# TF-USB.net
KiCad netlist of a schematic drawn in Altium Designer
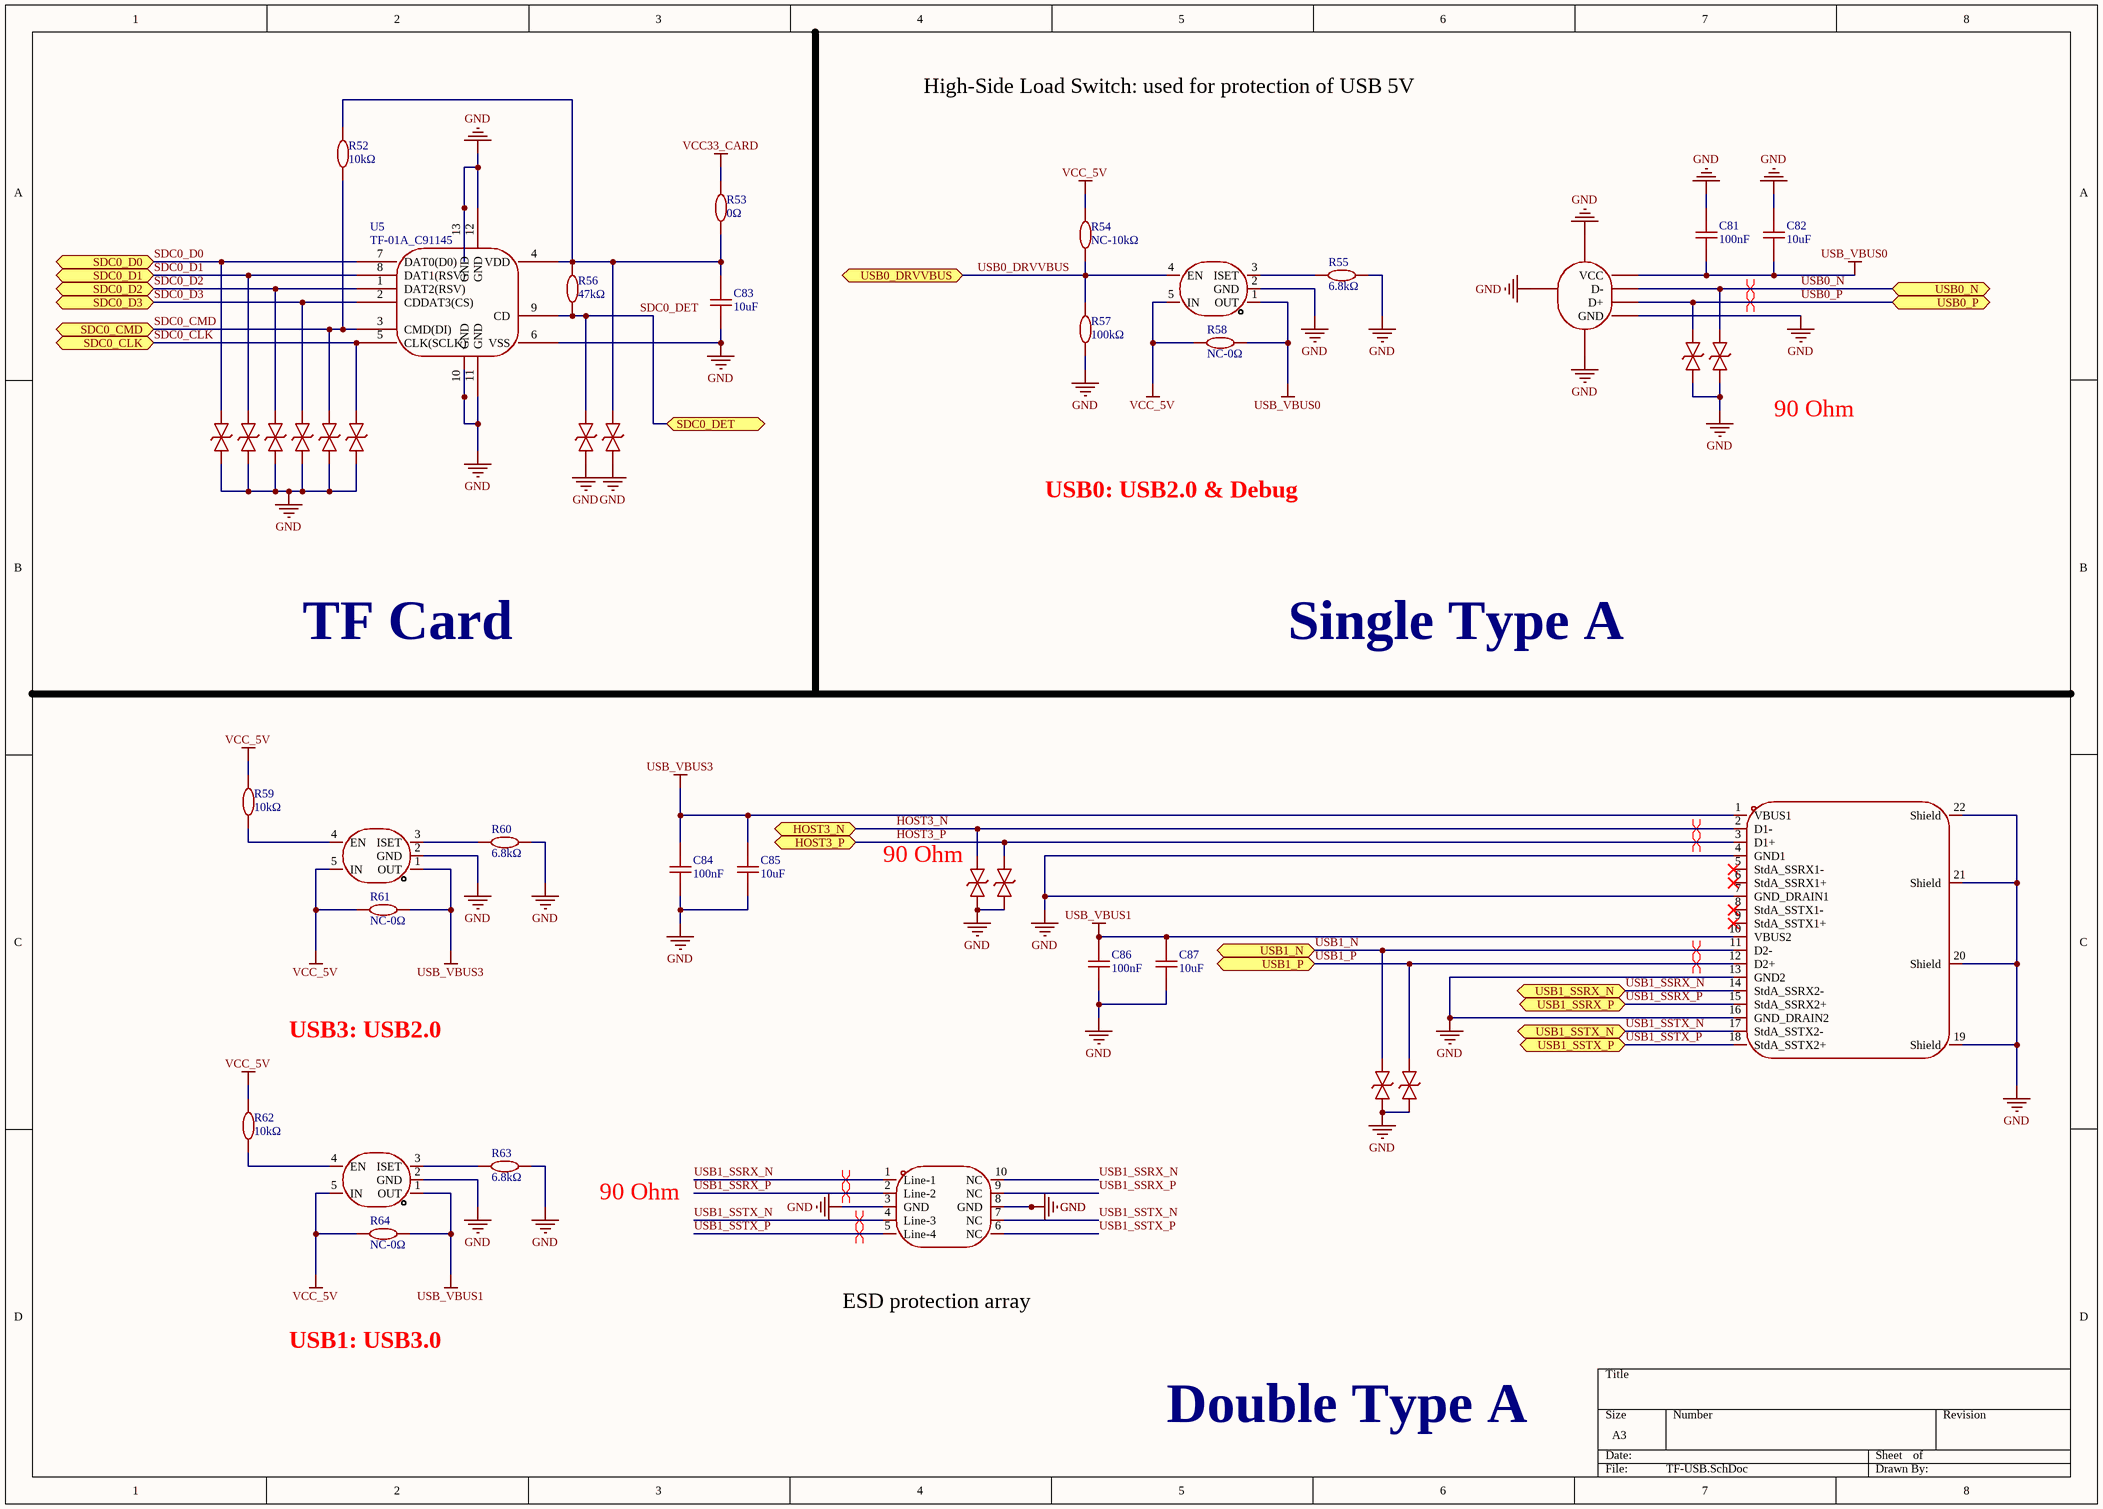
[diagram p0: TF-USB.SchDoc]

(export (version "E")
  (design (tool "Eeschema 10.0.6"))
  (components
    (comp (ref "C81")
      (value "100nF")
      (footprint "C0402")
      (description "50V 100nF X7R ±10% 0402 Ceramic Capacitors ROHS")
      (libsource (lib "RLC") (part "100nF"))
    )
    (comp (ref "C82")
      (value "10uF")
      (footprint "C0603")
      (description "10V 10uF X5R ±10% 0603 Ceramic Capacitors ROHS")
      (libsource (lib "RLC") (part "10uF"))
    )
    (comp (ref "C83")
      (value "10uF")
      (footprint "C0603")
      (description "10V 10uF X5R ±10% 0603 Ceramic Capacitors ROHS")
      (libsource (lib "RLC") (part "10uF"))
    )
    (comp (ref "C84")
      (value "100nF")
      (footprint "C0402")
      (description "50V 100nF X7R ±10% 0402 Ceramic Capacitors ROHS")
      (libsource (lib "RLC") (part "100nF"))
    )
    (comp (ref "C85")
      (value "10uF")
      (footprint "C0603")
      (description "10V 10uF X5R ±10% 0603 Ceramic Capacitors ROHS")
      (libsource (lib "RLC") (part "10uF"))
    )
    (comp (ref "C86")
      (value "100nF")
      (footprint "C0402")
      (description "50V 100nF X7R ±10% 0402 Ceramic Capacitors ROHS")
      (libsource (lib "RLC") (part "100nF"))
    )
    (comp (ref "C87")
      (value "10uF")
      (footprint "C0603")
      (description "10V 10uF X5R ±10% 0603 Ceramic Capacitors ROHS")
      (libsource (lib "RLC") (part "10uF"))
    )
    (comp (ref "D6")
      (value "AZ1045-04F.R7G")
      (footprint "DFN2510-10_L2.5-W1.0-P0.50-BL")
      (description "3.5A@8/20us 30W@8/20us 12V 6V 5V DFN2510-10 TVS Diodes ROHS")
      (fields (field (name "MANUFACTURER") "AMAZING(晶焱)"))
      (libsource (lib "IC") (part "AZ1045-04F.R7G"))
    )
    (comp (ref "R52")
      (value "10kΩ")
      (footprint "R0402")
      (description "62.5mW 10kΩ 50V ±100ppm/℃ Thick Film Resistor ±1% 0402 Chip Resistor - Surface Mount ROHS")
      (libsource (lib "RLC") (part "10kΩ"))
    )
    (comp (ref "R53")
      (value "0Ω")
      (footprint "R0402")
      (description "0Ω 62.5mW 50V Thick Film Resistor ±1% 0402 Chip Resistor - Surface Mount ROHS")
      (libsource (lib "RLC") (part "0Ω"))
    )
    (comp (ref "R54")
      (value "NC-10kΩ")
      (footprint "R0402")
      (description "62.5mW 10kΩ 50V ±100ppm/℃ Thick Film Resistor ±1% 0402 Chip Resistor - Surface Mount ROHS")
      (libsource (lib "RLC") (part "10kΩ"))
    )
    (comp (ref "R55")
      (value "6.8kΩ")
      (footprint "R0402")
      (description "62.5mW 6.8kΩ 50V ±100ppm/℃ Thick Film Resistor ±1% 0402 Chip Resistor - Surface Mount ROHS")
      (libsource (lib "RLC") (part "6.8kΩ"))
    )
    (comp (ref "R56")
      (value "47kΩ")
      (footprint "R0402")
      (description "62.5mW 47kΩ 50V ±100ppm/℃ Thick Film Resistor ±1% 0402 Chip Resistor - Surface Mount ROHS")
      (libsource (lib "RLC") (part "47kΩ"))
    )
    (comp (ref "R57")
      (value "100kΩ")
      (footprint "R0402")
      (description "100kΩ 62.5mW 50V ±100ppm/℃ Thick Film Resistor ±1% 0402 Chip Resistor - Surface Mount ROHS")
      (libsource (lib "RLC") (part "100kΩ"))
    )
    (comp (ref "R58")
      (value "NC-0Ω")
      (footprint "R0402")
      (description "0Ω 62.5mW 50V Thick Film Resistor ±1% 0402 Chip Resistor - Surface Mount ROHS")
      (libsource (lib "RLC") (part "0Ω"))
    )
    (comp (ref "R59")
      (value "10kΩ")
      (footprint "R0402")
      (description "62.5mW 10kΩ 50V ±100ppm/℃ Thick Film Resistor ±1% 0402 Chip Resistor - Surface Mount ROHS")
      (libsource (lib "RLC") (part "10kΩ"))
    )
    (comp (ref "R60")
      (value "6.8kΩ")
      (footprint "R0402")
      (description "62.5mW 6.8kΩ 50V ±100ppm/℃ Thick Film Resistor ±1% 0402 Chip Resistor - Surface Mount ROHS")
      (libsource (lib "RLC") (part "6.8kΩ"))
    )
    (comp (ref "R61")
      (value "NC-0Ω")
      (footprint "R0402")
      (description "0Ω 62.5mW 50V Thick Film Resistor ±1% 0402 Chip Resistor - Surface Mount ROHS")
      (libsource (lib "RLC") (part "0Ω"))
    )
    (comp (ref "R62")
      (value "10kΩ")
      (footprint "R0402")
      (description "62.5mW 10kΩ 50V ±100ppm/℃ Thick Film Resistor ±1% 0402 Chip Resistor - Surface Mount ROHS")
      (libsource (lib "RLC") (part "10kΩ"))
    )
    (comp (ref "R63")
      (value "6.8kΩ")
      (footprint "R0402")
      (description "62.5mW 6.8kΩ 50V ±100ppm/℃ Thick Film Resistor ±1% 0402 Chip Resistor - Surface Mount ROHS")
      (libsource (lib "RLC") (part "6.8kΩ"))
    )
    (comp (ref "R64")
      (value "NC-0Ω")
      (footprint "R0402")
      (description "0Ω 62.5mW 50V Thick Film Resistor ±1% 0402 Chip Resistor - Surface Mount ROHS")
      (libsource (lib "RLC") (part "0Ω"))
    )
    (comp (ref "U5")
      (value "TF-01A_C91145")
      (footprint "TF-SMD_TF-01A")
      (description "Push-Push 1.85mm Connector and Ejector MicroSD Card (TF Card) SMD PC Card Sockets ROHS")
      (libsource (lib "IC") (part "TF-01A_C91145"))
    )
    (comp (ref "U13")
      (value "SY6280AAC")
      (footprint "SOT-23-5_L3.0-W1.7-P0.95-LS2.8-BL")
      (description "1 Active High High Side Switch SOT-23-5 Power Distribution Switches, Load Drivers ROHS")
      (fields (field (name "MANUFACTURER") "Silergy(矽力杰)"))
      (libsource (lib "Switch") (part "SY6280AAC_C55136"))
    )
    (comp (ref "U14")
      (value "ESD5451N")
      (footprint "DFN1006-2L-BI")
      (description "9A 9.8V 8V Bidirectional 5V DFN1006-2L TVS Diodes ROHS")
      (fields (field (name "MANUFACTURER") "HXY MOSFET(华轩阳电子)"))
      (libsource (lib "LED") (part "ESD5451N_C5261080"))
    )
    (comp (ref "U15")
      (value "ESD5451N")
      (footprint "DFN1006-2L-BI")
      (description "9A 9.8V 8V Bidirectional 5V DFN1006-2L TVS Diodes ROHS")
      (fields (field (name "MANUFACTURER") "HXY MOSFET(华轩阳电子)"))
      (libsource (lib "LED") (part "ESD5451N_C5261080"))
    )
    (comp (ref "U16")
      (value "ESD5451N")
      (footprint "DFN1006-2L-BI")
      (description "9A 9.8V 8V Bidirectional 5V DFN1006-2L TVS Diodes ROHS")
      (fields (field (name "MANUFACTURER") "HXY MOSFET(华轩阳电子)"))
      (libsource (lib "LED") (part "ESD5451N_C5261080"))
    )
    (comp (ref "U17")
      (value "ESD5451N")
      (footprint "DFN1006-2L-BI")
      (description "9A 9.8V 8V Bidirectional 5V DFN1006-2L TVS Diodes ROHS")
      (fields (field (name "MANUFACTURER") "HXY MOSFET(华轩阳电子)"))
      (libsource (lib "LED") (part "ESD5451N_C5261080"))
    )
    (comp (ref "U18")
      (value "ESD5451N")
      (footprint "DFN1006-2L-BI")
      (description "9A 9.8V 8V Bidirectional 5V DFN1006-2L TVS Diodes ROHS")
      (fields (field (name "MANUFACTURER") "HXY MOSFET(华轩阳电子)"))
      (libsource (lib "LED") (part "ESD5451N_C5261080"))
    )
    (comp (ref "U19")
      (value "ESD5451N")
      (footprint "DFN1006-2L-BI")
      (description "9A 9.8V 8V Bidirectional 5V DFN1006-2L TVS Diodes ROHS")
      (fields (field (name "MANUFACTURER") "HXY MOSFET(华轩阳电子)"))
      (libsource (lib "LED") (part "ESD5451N_C5261080"))
    )
    (comp (ref "U20")
      (value "ESD5451N")
      (footprint "DFN1006-2L-BI")
      (description "9A 9.8V 8V Bidirectional 5V DFN1006-2L TVS Diodes ROHS")
      (fields (field (name "MANUFACTURER") "HXY MOSFET(华轩阳电子)"))
      (libsource (lib "LED") (part "ESD5451N_C5261080"))
    )
    (comp (ref "U21")
      (value "ESD5451N")
      (footprint "DFN1006-2L-BI")
      (description "9A 9.8V 8V Bidirectional 5V DFN1006-2L TVS Diodes ROHS")
      (fields (field (name "MANUFACTURER") "HXY MOSFET(华轩阳电子)"))
      (libsource (lib "LED") (part "ESD5451N_C5261080"))
    )
    (comp (ref "U22")
      (value "ESD5451N")
      (footprint "DFN1006-2L-BI")
      (description "9A 9.8V 8V Bidirectional 5V DFN1006-2L TVS Diodes ROHS")
      (fields (field (name "MANUFACTURER") "HXY MOSFET(华轩阳电子)"))
      (libsource (lib "LED") (part "ESD5451N_C5261080"))
    )
    (comp (ref "U23")
      (value "ESD5451N")
      (footprint "DFN1006-2L-BI")
      (description "9A 9.8V 8V Bidirectional 5V DFN1006-2L TVS Diodes ROHS")
      (fields (field (name "MANUFACTURER") "HXY MOSFET(华轩阳电子)"))
      (libsource (lib "LED") (part "ESD5451N_C5261080"))
    )
    (comp (ref "U24")
      (value "ESD5451N")
      (footprint "DFN1006-2L-BI")
      (description "9A 9.8V 8V Bidirectional 5V DFN1006-2L TVS Diodes ROHS")
      (fields (field (name "MANUFACTURER") "HXY MOSFET(华轩阳电子)"))
      (libsource (lib "LED") (part "ESD5451N_C5261080"))
    )
    (comp (ref "U25")
      (value "ESD5451N")
      (footprint "DFN1006-2L-BI")
      (description "9A 9.8V 8V Bidirectional 5V DFN1006-2L TVS Diodes ROHS")
      (fields (field (name "MANUFACTURER") "HXY MOSFET(华轩阳电子)"))
      (libsource (lib "LED") (part "ESD5451N_C5261080"))
    )
    (comp (ref "U26")
      (value "SY6280AAC")
      (footprint "SOT-23-5_L3.0-W1.7-P0.95-LS2.8-BL")
      (description "1 Active High High Side Switch SOT-23-5 Power Distribution Switches, Load Drivers ROHS")
      (fields (field (name "MANUFACTURER") "Silergy(矽力杰)"))
      (libsource (lib "Switch") (part "SY6280AAC_C55136"))
    )
    (comp (ref "U27")
      (value "ESD5451N")
      (footprint "DFN1006-2L-BI")
      (description "9A 9.8V 8V Bidirectional 5V DFN1006-2L TVS Diodes ROHS")
      (fields (field (name "MANUFACTURER") "HXY MOSFET(华轩阳电子)"))
      (libsource (lib "LED") (part "ESD5451N_C5261080"))
    )
    (comp (ref "U28")
      (value "ESD5451N")
      (footprint "DFN1006-2L-BI")
      (description "9A 9.8V 8V Bidirectional 5V DFN1006-2L TVS Diodes ROHS")
      (fields (field (name "MANUFACTURER") "HXY MOSFET(华轩阳电子)"))
      (libsource (lib "LED") (part "ESD5451N_C5261080"))
    )
    (comp (ref "U29")
      (value "SY6280AAC")
      (footprint "SOT-23-5_L3.0-W1.7-P0.95-LS2.8-BL")
      (description "1 Active High High Side Switch SOT-23-5 Power Distribution Switches, Load Drivers ROHS")
      (fields (field (name "MANUFACTURER") "Silergy(矽力杰)"))
      (libsource (lib "Switch") (part "SY6280AAC_C55136"))
    )
    (comp (ref "USB1")
      (value "USB-303WSD-BRY")
      (footprint "USB-A-TH_XUNPU_USB-303WSD-BRY")
      (description "USB 3.0 2 9Px2 -30℃~+85℃ Type-A Through Hole,Right Angle USB, DVI, HDMI Connector Assemblies ROHS")
      (fields (field (name "MANUFACTURER") "XUNPU(讯普)"))
      (libsource (lib "Connector") (part "USB-303WSD-BRY"))
    )
    (comp (ref "USB2")
      (value "906-162A1011D10200")
      (footprint "USB-A-TH_4P-P1.40-V-F-C39416")
      (description "USB 2.0 1 4P Type-A Through Hole USB, DVI, HDMI Connector Assemblies ROHS")
      (fields (field (name "MANUFACTURER") "精拓金"))
      (libsource (lib "Connector") (part "906-162A1011D10200"))
    )
  )
  (nets
    (net (code "1") (name "/HOST3_N") (class "Default")
      (node (ref "U24") (pin "2") (pinfunction "2_2") (pintype "passive"))
      (node (ref "USB1") (pin "2") (pinfunction "D1-_2") (pintype "passive"))
    )
    (net (code "2") (name "/HOST3_P") (class "Default")
      (node (ref "U25") (pin "2") (pinfunction "2_2") (pintype "passive"))
      (node (ref "USB1") (pin "3") (pinfunction "D1+_3") (pintype "passive"))
    )
    (net (code "3") (name "/SDC0_CLK") (class "Default")
      (node (ref "U21") (pin "2") (pinfunction "2_2") (pintype "passive"))
      (node (ref "U5") (pin "5") (pinfunction "CLK(SCLK)_5") (pintype "passive"))
    )
    (net (code "4") (name "/SDC0_CMD") (class "Default")
      (node (ref "R52") (pin "1") (pinfunction "1_1") (pintype "passive"))
      (node (ref "U20") (pin "2") (pinfunction "2_2") (pintype "passive"))
      (node (ref "U5") (pin "3") (pinfunction "CMD(DI)_3") (pintype "passive"))
    )
    (net (code "5") (name "/SDC0_D0") (class "Default")
      (node (ref "U16") (pin "2") (pinfunction "2_2") (pintype "passive"))
      (node (ref "U5") (pin "7") (pinfunction "DAT0(D0)_7") (pintype "passive"))
    )
    (net (code "6") (name "/SDC0_D1") (class "Default")
      (node (ref "U17") (pin "2") (pinfunction "2_2") (pintype "passive"))
      (node (ref "U5") (pin "8") (pinfunction "DAT1(RSV)_8") (pintype "passive"))
    )
    (net (code "7") (name "/SDC0_D2") (class "Default")
      (node (ref "U18") (pin "2") (pinfunction "2_2") (pintype "passive"))
      (node (ref "U5") (pin "1") (pinfunction "DAT2(RSV)_1") (pintype "passive"))
    )
    (net (code "8") (name "/SDC0_D3") (class "Default")
      (node (ref "U19") (pin "2") (pinfunction "2_2") (pintype "passive"))
      (node (ref "U5") (pin "2") (pinfunction "CDDAT3(CS)_2") (pintype "passive"))
    )
    (net (code "9") (name "/SDC0_DET") (class "Default")
      (node (ref "R56") (pin "1") (pinfunction "1_1") (pintype "passive"))
      (node (ref "U22") (pin "2") (pinfunction "2_2") (pintype "passive"))
      (node (ref "U5") (pin "9") (pinfunction "CD_9") (pintype "passive"))
    )
    (net (code "10") (name "/USB0_DRVVBUS") (class "Default")
      (node (ref "R54") (pin "1") (pinfunction "1_1") (pintype "passive"))
      (node (ref "R57") (pin "2") (pinfunction "2_2") (pintype "passive"))
      (node (ref "U13") (pin "4") (pinfunction "EN_4") (pintype "passive"))
    )
    (net (code "11") (name "/USB0_N") (class "Default")
      (node (ref "U15") (pin "2") (pinfunction "2_2") (pintype "passive"))
      (node (ref "USB2") (pin "2") (pinfunction "D-_2") (pintype "passive"))
    )
    (net (code "12") (name "/USB0_P") (class "Default")
      (node (ref "U14") (pin "2") (pinfunction "2_2") (pintype "passive"))
      (node (ref "USB2") (pin "3") (pinfunction "D+_3") (pintype "passive"))
    )
    (net (code "13") (name "/USB1_N") (class "Default")
      (node (ref "U27") (pin "2") (pinfunction "2_2") (pintype "passive"))
      (node (ref "USB1") (pin "11") (pinfunction "D2-_11") (pintype "passive"))
    )
    (net (code "14") (name "/USB1_P") (class "Default")
      (node (ref "U28") (pin "2") (pinfunction "2_2") (pintype "passive"))
      (node (ref "USB1") (pin "12") (pinfunction "D2+_12") (pintype "passive"))
    )
    (net (code "15") (name "/USB1_SSRX_N") (class "Default")
      (node (ref "D6") (pin "1") (pinfunction "Line-1_1") (pintype "passive"))
      (node (ref "D6") (pin "10") (pinfunction "NC_10") (pintype "passive"))
      (node (ref "USB1") (pin "14") (pinfunction "StdA_SSRX2-_14") (pintype "passive"))
    )
    (net (code "16") (name "/USB1_SSRX_P") (class "Default")
      (node (ref "D6") (pin "2") (pinfunction "Line-2_2") (pintype "passive"))
      (node (ref "D6") (pin "9") (pinfunction "NC_9") (pintype "passive"))
      (node (ref "USB1") (pin "15") (pinfunction "StdA_SSRX2+_15") (pintype "passive"))
    )
    (net (code "17") (name "/USB1_SSTX_N") (class "Default")
      (node (ref "D6") (pin "4") (pinfunction "Line-3_4") (pintype "passive"))
      (node (ref "D6") (pin "7") (pinfunction "NC_7") (pintype "passive"))
      (node (ref "USB1") (pin "17") (pinfunction "StdA_SSTX2-_17") (pintype "passive"))
    )
    (net (code "18") (name "/USB1_SSTX_P") (class "Default")
      (node (ref "D6") (pin "5") (pinfunction "Line-4_5") (pintype "passive"))
      (node (ref "D6") (pin "6") (pinfunction "NC_6") (pintype "passive"))
      (node (ref "USB1") (pin "18") (pinfunction "StdA_SSTX2+_18") (pintype "passive"))
    )
    (net (code "19") (name "GND") (class "Default")
      (node (ref "C81") (pin "2") (pinfunction "2_2") (pintype "passive"))
      (node (ref "C82") (pin "2") (pinfunction "2_2") (pintype "passive"))
      (node (ref "C83") (pin "1") (pinfunction "1_1") (pintype "passive"))
      (node (ref "C84") (pin "1") (pinfunction "1_1") (pintype "passive"))
      (node (ref "C85") (pin "1") (pinfunction "1_1") (pintype "passive"))
      (node (ref "C86") (pin "1") (pinfunction "1_1") (pintype "passive"))
      (node (ref "C87") (pin "1") (pinfunction "1_1") (pintype "passive"))
      (node (ref "D6") (pin "3") (pinfunction "GND_3") (pintype "passive"))
      (node (ref "D6") (pin "8") (pinfunction "GND_8") (pintype "passive"))
      (node (ref "R55") (pin "2") (pinfunction "2_2") (pintype "passive"))
      (node (ref "R57") (pin "1") (pinfunction "1_1") (pintype "passive"))
      (node (ref "R60") (pin "2") (pinfunction "2_2") (pintype "passive"))
      (node (ref "R63") (pin "2") (pinfunction "2_2") (pintype "passive"))
      (node (ref "U13") (pin "2") (pinfunction "GND_2") (pintype "passive"))
      (node (ref "U14") (pin "1") (pinfunction "1_1") (pintype "passive"))
      (node (ref "U15") (pin "1") (pinfunction "1_1") (pintype "passive"))
      (node (ref "U16") (pin "1") (pinfunction "1_1") (pintype "passive"))
      (node (ref "U17") (pin "1") (pinfunction "1_1") (pintype "passive"))
      (node (ref "U18") (pin "1") (pinfunction "1_1") (pintype "passive"))
      (node (ref "U19") (pin "1") (pinfunction "1_1") (pintype "passive"))
      (node (ref "U20") (pin "1") (pinfunction "1_1") (pintype "passive"))
      (node (ref "U21") (pin "1") (pinfunction "1_1") (pintype "passive"))
      (node (ref "U22") (pin "1") (pinfunction "1_1") (pintype "passive"))
      (node (ref "U23") (pin "1") (pinfunction "1_1") (pintype "passive"))
      (node (ref "U24") (pin "1") (pinfunction "1_1") (pintype "passive"))
      (node (ref "U25") (pin "1") (pinfunction "1_1") (pintype "passive"))
      (node (ref "U26") (pin "2") (pinfunction "GND_2") (pintype "passive"))
      (node (ref "U27") (pin "1") (pinfunction "1_1") (pintype "passive"))
      (node (ref "U28") (pin "1") (pinfunction "1_1") (pintype "passive"))
      (node (ref "U29") (pin "2") (pinfunction "GND_2") (pintype "passive"))
      (node (ref "U5") (pin "10") (pinfunction "GND_10") (pintype "passive"))
      (node (ref "U5") (pin "11") (pinfunction "GND_11") (pintype "passive"))
      (node (ref "U5") (pin "12") (pinfunction "GND_12") (pintype "passive"))
      (node (ref "U5") (pin "13") (pinfunction "GND_13") (pintype "passive"))
      (node (ref "U5") (pin "6") (pinfunction "VSS_6") (pintype "passive"))
      (node (ref "USB1") (pin "13") (pinfunction "GND2_13") (pintype "passive"))
      (node (ref "USB1") (pin "16") (pinfunction "GND_DRAIN2_16") (pintype "passive"))
      (node (ref "USB1") (pin "19") (pinfunction "Shield_19") (pintype "passive"))
      (node (ref "USB1") (pin "20") (pinfunction "Shield_20") (pintype "passive"))
      (node (ref "USB1") (pin "21") (pinfunction "Shield_21") (pintype "passive"))
      (node (ref "USB1") (pin "22") (pinfunction "Shield_22") (pintype "passive"))
      (node (ref "USB1") (pin "4") (pinfunction "GND1_4") (pintype "passive"))
      (node (ref "USB1") (pin "7") (pinfunction "GND_DRAIN1_7") (pintype "passive"))
      (node (ref "USB2") (pin "4") (pinfunction "GND_4") (pintype "passive"))
      (node (ref "USB2") (pin "5") (pinfunction "5_5") (pintype "passive"))
      (node (ref "USB2") (pin "6") (pinfunction "6_6") (pintype "passive"))
      (node (ref "USB2") (pin "7") (pinfunction "7_7") (pintype "passive"))
    )
    (net (code "20") (name "Net-(U5-VDD)") (class "Default")
      (node (ref "C83") (pin "2") (pinfunction "2_2") (pintype "passive"))
      (node (ref "R52") (pin "2") (pinfunction "2_2") (pintype "passive"))
      (node (ref "R53") (pin "1") (pinfunction "1_1") (pintype "passive"))
      (node (ref "R56") (pin "2") (pinfunction "2_2") (pintype "passive"))
      (node (ref "U23") (pin "2") (pinfunction "2_2") (pintype "passive"))
      (node (ref "U5") (pin "4") (pinfunction "VDD_4") (pintype "passive"))
    )
    (net (code "21") (name "Net-(U13-ISET)") (class "Default")
      (node (ref "R55") (pin "1") (pinfunction "1_1") (pintype "passive"))
      (node (ref "U13") (pin "3") (pinfunction "ISET_3") (pintype "passive"))
    )
    (net (code "22") (name "Net-(U26-EN)") (class "Default")
      (node (ref "R59") (pin "1") (pinfunction "1_1") (pintype "passive"))
      (node (ref "U26") (pin "4") (pinfunction "EN_4") (pintype "passive"))
    )
    (net (code "23") (name "Net-(U26-ISET)") (class "Default")
      (node (ref "R60") (pin "1") (pinfunction "1_1") (pintype "passive"))
      (node (ref "U26") (pin "3") (pinfunction "ISET_3") (pintype "passive"))
    )
    (net (code "24") (name "Net-(U29-EN)") (class "Default")
      (node (ref "R62") (pin "1") (pinfunction "1_1") (pintype "passive"))
      (node (ref "U29") (pin "4") (pinfunction "EN_4") (pintype "passive"))
    )
    (net (code "25") (name "Net-(U29-ISET)") (class "Default")
      (node (ref "R63") (pin "1") (pinfunction "1_1") (pintype "passive"))
      (node (ref "U29") (pin "3") (pinfunction "ISET_3") (pintype "passive"))
    )
    (net (code "26") (name "USB_VBUS0") (class "Default")
      (node (ref "C81") (pin "1") (pinfunction "1_1") (pintype "passive"))
      (node (ref "C82") (pin "1") (pinfunction "1_1") (pintype "passive"))
      (node (ref "R58") (pin "1") (pinfunction "1_1") (pintype "passive"))
      (node (ref "U13") (pin "1") (pinfunction "OUT_1") (pintype "passive"))
      (node (ref "USB2") (pin "1") (pinfunction "VCC_1") (pintype "passive"))
    )
    (net (code "27") (name "USB_VBUS1") (class "Default")
      (node (ref "C86") (pin "2") (pinfunction "2_2") (pintype "passive"))
      (node (ref "C87") (pin "2") (pinfunction "2_2") (pintype "passive"))
      (node (ref "R64") (pin "1") (pinfunction "1_1") (pintype "passive"))
      (node (ref "U29") (pin "1") (pinfunction "OUT_1") (pintype "passive"))
      (node (ref "USB1") (pin "10") (pinfunction "VBUS2_10") (pintype "passive"))
    )
    (net (code "28") (name "USB_VBUS3") (class "Default")
      (node (ref "C84") (pin "2") (pinfunction "2_2") (pintype "passive"))
      (node (ref "C85") (pin "2") (pinfunction "2_2") (pintype "passive"))
      (node (ref "R61") (pin "1") (pinfunction "1_1") (pintype "passive"))
      (node (ref "U26") (pin "1") (pinfunction "OUT_1") (pintype "passive"))
      (node (ref "USB1") (pin "1") (pinfunction "VBUS1_1") (pintype "passive"))
    )
    (net (code "29") (name "VCC33_CARD") (class "Default")
      (node (ref "R53") (pin "2") (pinfunction "2_2") (pintype "passive"))
    )
    (net (code "30") (name "VCC_5V") (class "Default")
      (node (ref "R54") (pin "2") (pinfunction "2_2") (pintype "passive"))
      (node (ref "R58") (pin "2") (pinfunction "2_2") (pintype "passive"))
      (node (ref "R59") (pin "2") (pinfunction "2_2") (pintype "passive"))
      (node (ref "R61") (pin "2") (pinfunction "2_2") (pintype "passive"))
      (node (ref "R62") (pin "2") (pinfunction "2_2") (pintype "passive"))
      (node (ref "R64") (pin "2") (pinfunction "2_2") (pintype "passive"))
      (node (ref "U13") (pin "5") (pinfunction "IN_5") (pintype "passive"))
      (node (ref "U26") (pin "5") (pinfunction "IN_5") (pintype "passive"))
      (node (ref "U29") (pin "5") (pinfunction "IN_5") (pintype "passive"))
    )
    (net (code "31") (name "unconnected-(USB1-StdA_SSRX1+-Pad6)") (class "Default")
      (node (ref "USB1") (pin "6") (pinfunction "StdA_SSRX1+_6") (pintype "passive+no_connect"))
    )
    (net (code "32") (name "unconnected-(USB1-StdA_SSRX1--Pad5)") (class "Default")
      (node (ref "USB1") (pin "5") (pinfunction "StdA_SSRX1-_5") (pintype "passive+no_connect"))
    )
    (net (code "33") (name "unconnected-(USB1-StdA_SSTX1+-Pad9)") (class "Default")
      (node (ref "USB1") (pin "9") (pinfunction "StdA_SSTX1+_9") (pintype "passive+no_connect"))
    )
    (net (code "34") (name "unconnected-(USB1-StdA_SSTX1--Pad8)") (class "Default")
      (node (ref "USB1") (pin "8") (pinfunction "StdA_SSTX1-_8") (pintype "passive+no_connect"))
    )
  )
)
